# HEATER.net
KiCad netlist of a schematic drawn in Altium Designer
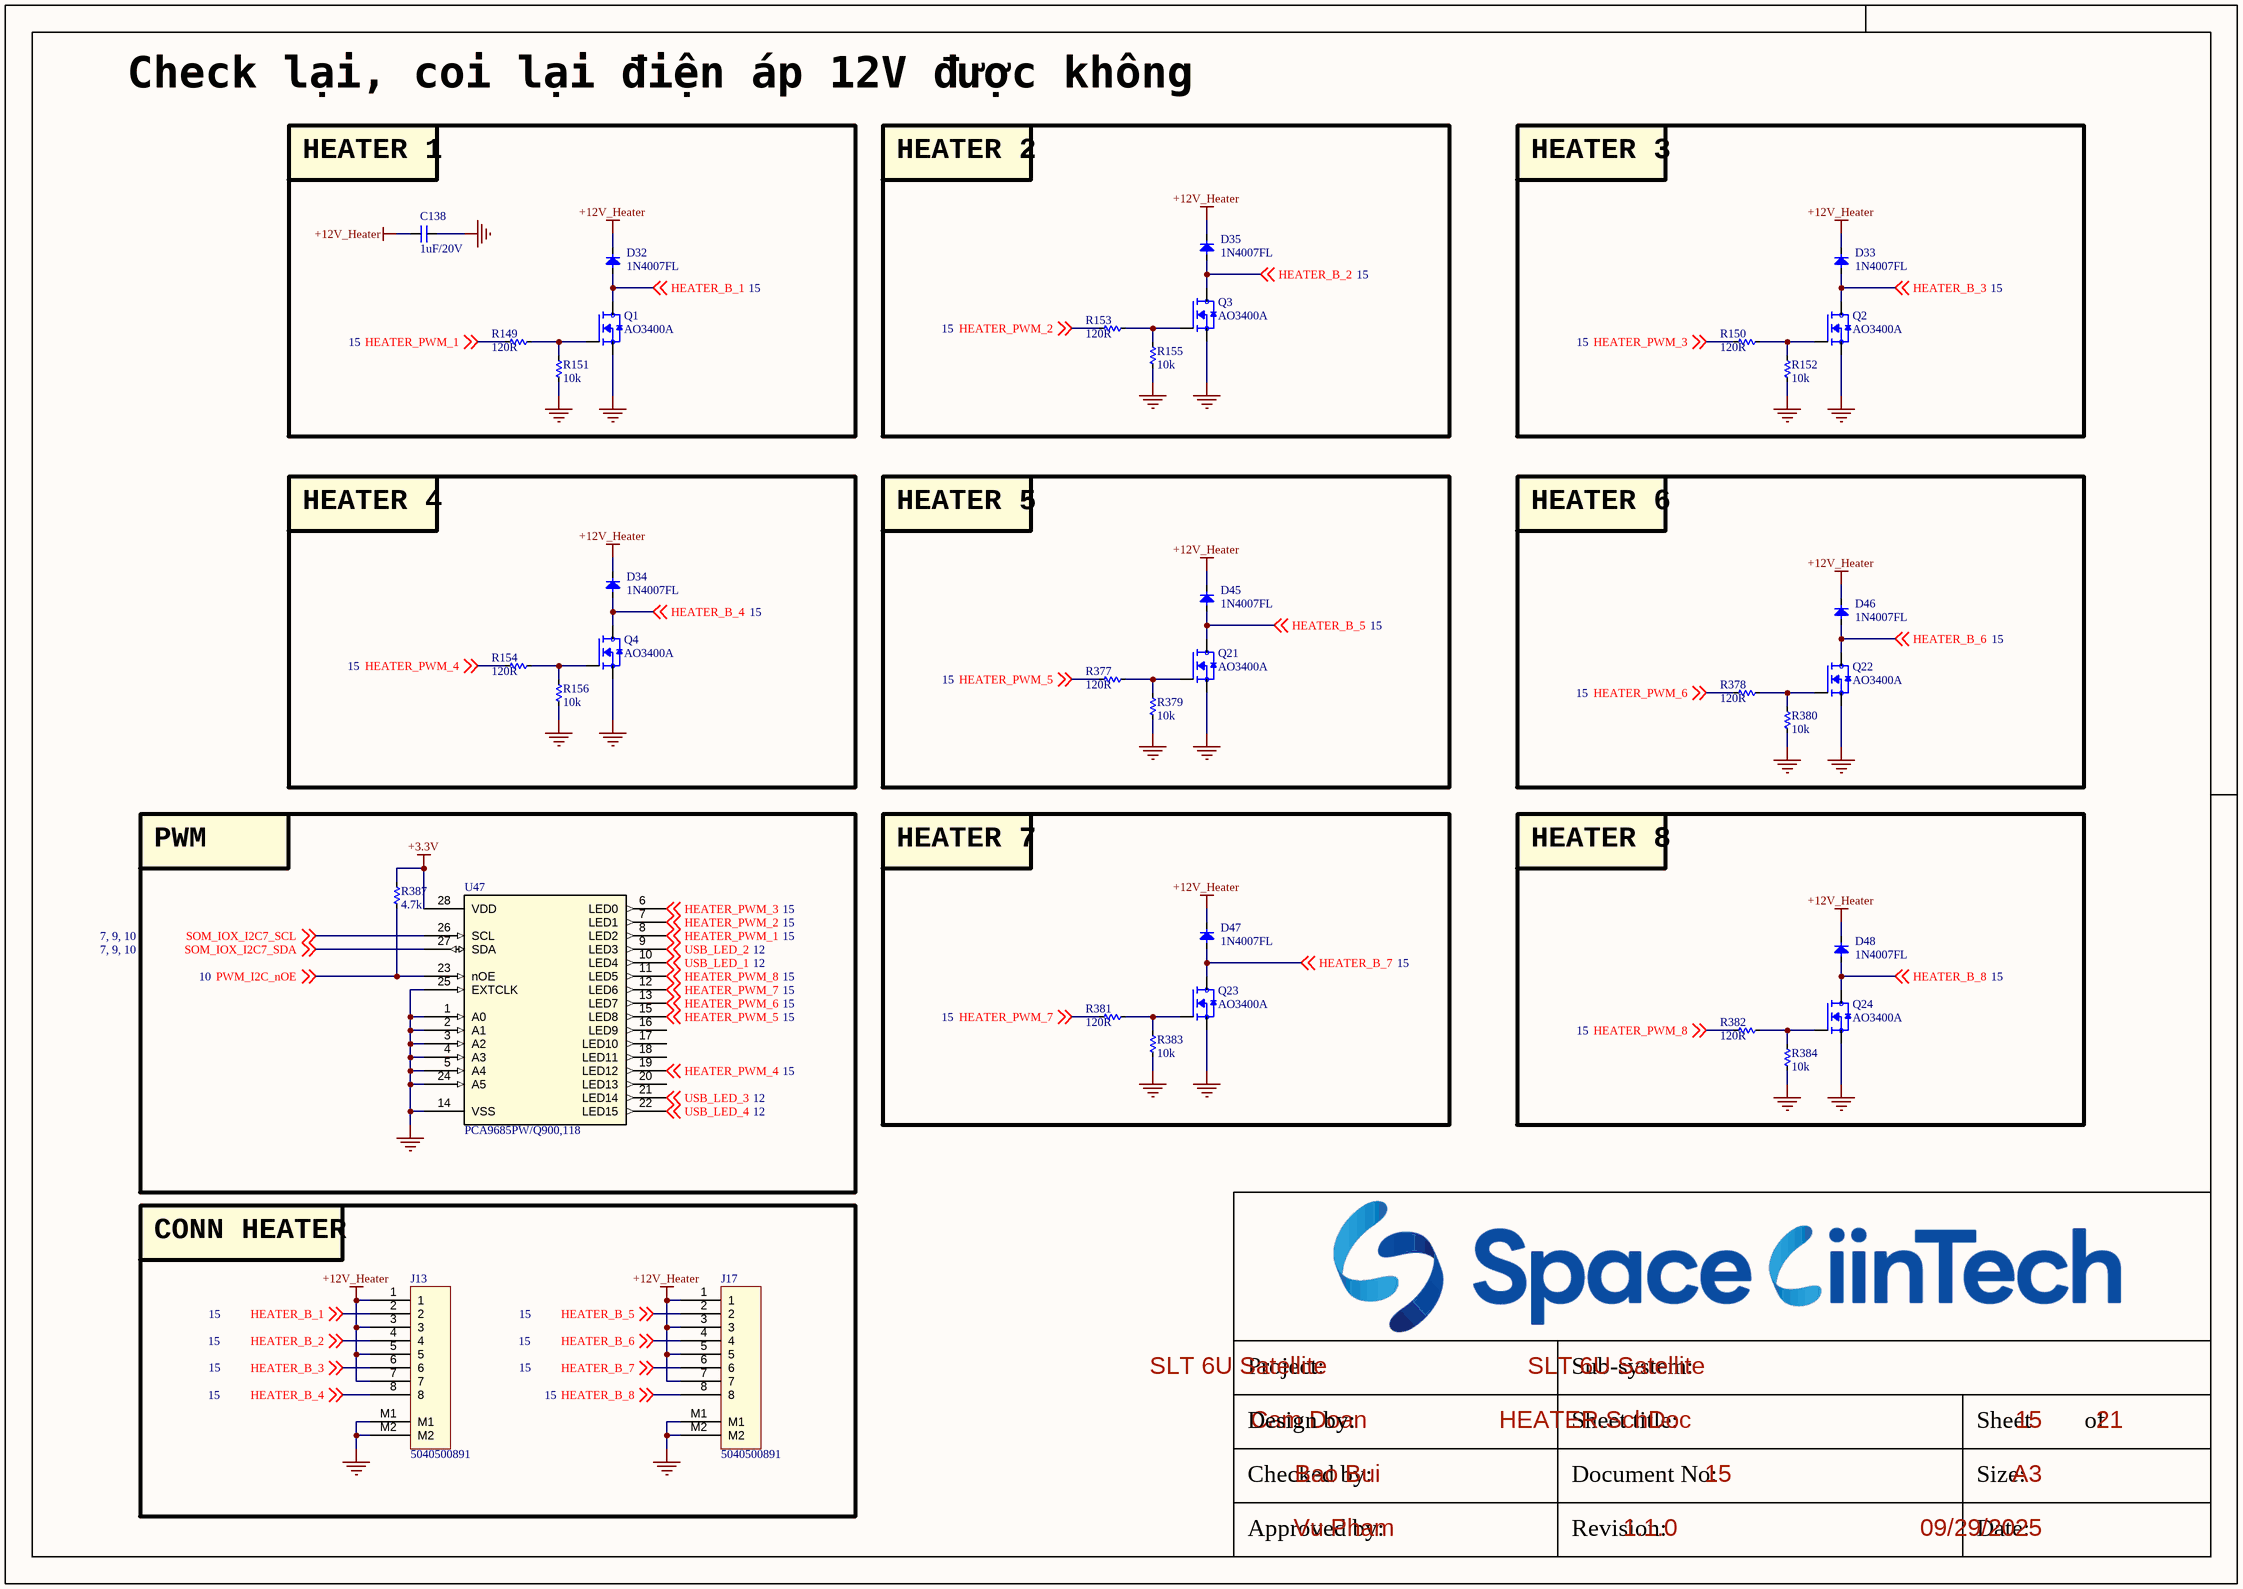
[diagram p0: HEATER.SchDoc]

(export (version "E")
  (design (tool "Eeschema 10.0.6"))
  (components
    (comp (ref "C138")
      (value "1uF/20V")
      (footprint "CAP_C_1005X60")
      (description "CAP CHIP")
      (libsource (lib "LABLIB") (part "_CAP_C_2"))
    )
    (comp (ref "D32")
      (value "1N4007FL")
      (footprint "SOD3717X145N")
      (description "Default Diode")
      (fields (field (name "PUBLISHER") "Altium Limited"))
      (libsource (lib "LABLIB") (part "Diode SMD"))
    )
    (comp (ref "D33")
      (value "1N4007FL")
      (footprint "SOD3717X145N")
      (description "Default Diode")
      (fields (field (name "PUBLISHER") "Altium Limited"))
      (libsource (lib "LABLIB") (part "Diode SMD"))
    )
    (comp (ref "D34")
      (value "1N4007FL")
      (footprint "SOD3717X145N")
      (description "Default Diode")
      (fields (field (name "PUBLISHER") "Altium Limited"))
      (libsource (lib "LABLIB") (part "Diode SMD"))
    )
    (comp (ref "D35")
      (value "1N4007FL")
      (footprint "SOD3717X145N")
      (description "Default Diode")
      (fields (field (name "PUBLISHER") "Altium Limited"))
      (libsource (lib "LABLIB") (part "Diode SMD"))
    )
    (comp (ref "D45")
      (value "1N4007FL")
      (footprint "SOD3717X145N")
      (description "Default Diode")
      (fields (field (name "PUBLISHER") "Altium Limited"))
      (libsource (lib "LABLIB") (part "Diode SMD"))
    )
    (comp (ref "D46")
      (value "1N4007FL")
      (footprint "SOD3717X145N")
      (description "Default Diode")
      (fields (field (name "PUBLISHER") "Altium Limited"))
      (libsource (lib "LABLIB") (part "Diode SMD"))
    )
    (comp (ref "D47")
      (value "1N4007FL")
      (footprint "SOD3717X145N")
      (description "Default Diode")
      (fields (field (name "PUBLISHER") "Altium Limited"))
      (libsource (lib "LABLIB") (part "Diode SMD"))
    )
    (comp (ref "D48")
      (value "1N4007FL")
      (footprint "SOD3717X145N")
      (description "Default Diode")
      (fields (field (name "PUBLISHER") "Altium Limited"))
      (libsource (lib "LABLIB") (part "Diode SMD"))
    )
    (comp (ref "J13")
      (value "5040500891")
      (footprint "MOLEX_5040500891")
      (libsource (lib "LABLIB") (part "Header 8x1_2M"))
    )
    (comp (ref "J17")
      (value "5040500891")
      (footprint "MOLEX_5040500891")
      (libsource (lib "LABLIB") (part "Header 8x1_2M"))
    )
    (comp (ref "Q1")
      (value "AO3400A")
      (footprint "SOT95P240X120-3N")
      (description "N-Channel 30 V 5.7A (Ta) 1.4W (Ta) Surface Mount SOT-23-3")
      (fields (field (name "MF") "Alpha & Omega Semiconductor"))
      (libsource (lib "new_component") (part "MOSFET_N"))
    )
    (comp (ref "Q2")
      (value "AO3400A")
      (footprint "SOT95P240X120-3N")
      (description "N-Channel 30 V 5.7A (Ta) 1.4W (Ta) Surface Mount SOT-23-3")
      (fields (field (name "MF") "Alpha & Omega Semiconductor"))
      (libsource (lib "new_component") (part "MOSFET_N"))
    )
    (comp (ref "Q3")
      (value "AO3400A")
      (footprint "SOT95P240X120-3N")
      (description "N-Channel 30 V 5.7A (Ta) 1.4W (Ta) Surface Mount SOT-23-3")
      (fields (field (name "MF") "Alpha & Omega Semiconductor"))
      (libsource (lib "new_component") (part "MOSFET_N"))
    )
    (comp (ref "Q4")
      (value "AO3400A")
      (footprint "SOT95P240X120-3N")
      (description "N-Channel 30 V 5.7A (Ta) 1.4W (Ta) Surface Mount SOT-23-3")
      (fields (field (name "MF") "Alpha & Omega Semiconductor"))
      (libsource (lib "new_component") (part "MOSFET_N"))
    )
    (comp (ref "Q21")
      (value "AO3400A")
      (footprint "SOT95P240X120-3N")
      (description "N-Channel 30 V 5.7A (Ta) 1.4W (Ta) Surface Mount SOT-23-3")
      (fields (field (name "MF") "Alpha & Omega Semiconductor"))
      (libsource (lib "new_component") (part "MOSFET_N"))
    )
    (comp (ref "Q22")
      (value "AO3400A")
      (footprint "SOT95P240X120-3N")
      (description "N-Channel 30 V 5.7A (Ta) 1.4W (Ta) Surface Mount SOT-23-3")
      (fields (field (name "MF") "Alpha & Omega Semiconductor"))
      (libsource (lib "new_component") (part "MOSFET_N"))
    )
    (comp (ref "Q23")
      (value "AO3400A")
      (footprint "SOT95P240X120-3N")
      (description "N-Channel 30 V 5.7A (Ta) 1.4W (Ta) Surface Mount SOT-23-3")
      (fields (field (name "MF") "Alpha & Omega Semiconductor"))
      (libsource (lib "new_component") (part "MOSFET_N"))
    )
    (comp (ref "Q24")
      (value "AO3400A")
      (footprint "SOT95P240X120-3N")
      (description "N-Channel 30 V 5.7A (Ta) 1.4W (Ta) Surface Mount SOT-23-3")
      (fields (field (name "MF") "Alpha & Omega Semiconductor"))
      (libsource (lib "new_component") (part "MOSFET_N"))
    )
    (comp (ref "R149")
      (value "120R")
      (footprint "RES_C_1005X40")
      (description "RES")
      (libsource (lib "LABLIB") (part "_RES_B_2"))
    )
    (comp (ref "R150")
      (value "120R")
      (footprint "RES_C_1005X40")
      (description "RES")
      (libsource (lib "LABLIB") (part "_RES_B_2"))
    )
    (comp (ref "R151")
      (value "10k")
      (footprint "RES_C_1005X40")
      (description "RES")
      (libsource (lib "LABLIB") (part "_RES_B_2"))
    )
    (comp (ref "R152")
      (value "10k")
      (footprint "RES_C_1005X40")
      (description "RES")
      (libsource (lib "LABLIB") (part "_RES_B_2"))
    )
    (comp (ref "R153")
      (value "120R")
      (footprint "RES_C_1005X40")
      (description "RES")
      (libsource (lib "LABLIB") (part "_RES_B_2"))
    )
    (comp (ref "R154")
      (value "120R")
      (footprint "RES_C_1005X40")
      (description "RES")
      (libsource (lib "LABLIB") (part "_RES_B_2"))
    )
    (comp (ref "R155")
      (value "10k")
      (footprint "RES_C_1005X40")
      (description "RES")
      (libsource (lib "LABLIB") (part "_RES_B_2"))
    )
    (comp (ref "R156")
      (value "10k")
      (footprint "RES_C_1005X40")
      (description "RES")
      (libsource (lib "LABLIB") (part "_RES_B_2"))
    )
    (comp (ref "R377")
      (value "120R")
      (footprint "RES_C_1005X40")
      (description "RES")
      (libsource (lib "LABLIB") (part "_RES_B_2"))
    )
    (comp (ref "R378")
      (value "120R")
      (footprint "RES_C_1005X40")
      (description "RES")
      (libsource (lib "LABLIB") (part "_RES_B_2"))
    )
    (comp (ref "R379")
      (value "10k")
      (footprint "RES_C_1005X40")
      (description "RES")
      (libsource (lib "LABLIB") (part "_RES_B_2"))
    )
    (comp (ref "R380")
      (value "10k")
      (footprint "RES_C_1005X40")
      (description "RES")
      (libsource (lib "LABLIB") (part "_RES_B_2"))
    )
    (comp (ref "R381")
      (value "120R")
      (footprint "RES_C_1005X40")
      (description "RES")
      (libsource (lib "LABLIB") (part "_RES_B_2"))
    )
    (comp (ref "R382")
      (value "120R")
      (footprint "RES_C_1005X40")
      (description "RES")
      (libsource (lib "LABLIB") (part "_RES_B_2"))
    )
    (comp (ref "R383")
      (value "10k")
      (footprint "RES_C_1005X40")
      (description "RES")
      (libsource (lib "LABLIB") (part "_RES_B_2"))
    )
    (comp (ref "R384")
      (value "10k")
      (footprint "RES_C_1005X40")
      (description "RES")
      (libsource (lib "LABLIB") (part "_RES_B_2"))
    )
    (comp (ref "R387")
      (value "4.7k")
      (footprint "RES_C_1005X40")
      (description "RES")
      (libsource (lib "LABLIB") (part "_RES_B_2"))
    )
    (comp (ref "U47")
      (value "PCA9685PW/Q900,118")
      (footprint "TSSOP28_SOT361-1_NXP")
      (description "No Description Available")
      (fields (field (name "COPYRIGHT") "Copyright (C) 2025 Ultra Librarian. All rights reserved."))
      (libsource (lib "LABLIB") (part "IC_PWM_PCA9685PW/Q900,118"))
    )
  )
  (nets
    (net (code "1") (name "+3.3V") (class "Default")
      (node (ref "R387") (pin "2") (pinfunction "2_2") (pintype "passive"))
      (node (ref "U47") (pin "28") (pinfunction "VDD_28") (pintype "power_in"))
    )
    (net (code "2") (name "+12V_Heater") (class "Default")
      (node (ref "C138") (pin "2") (pinfunction "2_2") (pintype "passive"))
      (node (ref "D32") (pin "1") (pinfunction "K_1") (pintype "passive"))
      (node (ref "D33") (pin "1") (pinfunction "K_1") (pintype "passive"))
      (node (ref "D34") (pin "1") (pinfunction "K_1") (pintype "passive"))
      (node (ref "D35") (pin "1") (pinfunction "K_1") (pintype "passive"))
      (node (ref "D45") (pin "1") (pinfunction "K_1") (pintype "passive"))
      (node (ref "D46") (pin "1") (pinfunction "K_1") (pintype "passive"))
      (node (ref "D47") (pin "1") (pinfunction "K_1") (pintype "passive"))
      (node (ref "D48") (pin "1") (pinfunction "K_1") (pintype "passive"))
      (node (ref "J13") (pin "1") (pinfunction "1_1") (pintype "passive"))
      (node (ref "J13") (pin "3") (pinfunction "3_3") (pintype "passive"))
      (node (ref "J13") (pin "5") (pinfunction "5_5") (pintype "passive"))
      (node (ref "J13") (pin "7") (pinfunction "7_7") (pintype "passive"))
      (node (ref "J17") (pin "1") (pinfunction "1_1") (pintype "passive"))
      (node (ref "J17") (pin "3") (pinfunction "3_3") (pintype "passive"))
      (node (ref "J17") (pin "5") (pinfunction "5_5") (pintype "passive"))
      (node (ref "J17") (pin "7") (pinfunction "7_7") (pintype "passive"))
    )
    (net (code "3") (name "GND") (class "Default")
      (node (ref "C138") (pin "1") (pinfunction "1_1") (pintype "passive"))
      (node (ref "J13") (pin "M1") (pinfunction "M1_M1") (pintype "passive"))
      (node (ref "J13") (pin "M2") (pinfunction "M2_M2") (pintype "passive"))
      (node (ref "J17") (pin "M1") (pinfunction "M1_M1") (pintype "passive"))
      (node (ref "J17") (pin "M2") (pinfunction "M2_M2") (pintype "passive"))
      (node (ref "Q1") (pin "2") (pinfunction "S_2") (pintype "passive"))
      (node (ref "Q2") (pin "2") (pinfunction "S_2") (pintype "passive"))
      (node (ref "Q21") (pin "2") (pinfunction "S_2") (pintype "passive"))
      (node (ref "Q22") (pin "2") (pinfunction "S_2") (pintype "passive"))
      (node (ref "Q23") (pin "2") (pinfunction "S_2") (pintype "passive"))
      (node (ref "Q24") (pin "2") (pinfunction "S_2") (pintype "passive"))
      (node (ref "Q3") (pin "2") (pinfunction "S_2") (pintype "passive"))
      (node (ref "Q4") (pin "2") (pinfunction "S_2") (pintype "passive"))
      (node (ref "R151") (pin "1") (pinfunction "1_1") (pintype "passive"))
      (node (ref "R152") (pin "1") (pinfunction "1_1") (pintype "passive"))
      (node (ref "R155") (pin "1") (pinfunction "1_1") (pintype "passive"))
      (node (ref "R156") (pin "1") (pinfunction "1_1") (pintype "passive"))
      (node (ref "R379") (pin "1") (pinfunction "1_1") (pintype "passive"))
      (node (ref "R380") (pin "1") (pinfunction "1_1") (pintype "passive"))
      (node (ref "R383") (pin "1") (pinfunction "1_1") (pintype "passive"))
      (node (ref "R384") (pin "1") (pinfunction "1_1") (pintype "passive"))
      (node (ref "U47") (pin "1") (pinfunction "A0_1") (pintype "input"))
      (node (ref "U47") (pin "14") (pinfunction "VSS_14") (pintype "power_in"))
      (node (ref "U47") (pin "2") (pinfunction "A1_2") (pintype "input"))
      (node (ref "U47") (pin "24") (pinfunction "A5_24") (pintype "input"))
      (node (ref "U47") (pin "25") (pinfunction "EXTCLK_25") (pintype "input"))
      (node (ref "U47") (pin "3") (pinfunction "A2_3") (pintype "input"))
      (node (ref "U47") (pin "4") (pinfunction "A3_4") (pintype "input"))
      (node (ref "U47") (pin "5") (pinfunction "A4_5") (pintype "input"))
    )
    (net (code "4") (name "HEATER_B_1") (class "Default")
      (node (ref "D32") (pin "2") (pinfunction "A_2") (pintype "passive"))
      (node (ref "J13") (pin "2") (pinfunction "2_2") (pintype "passive"))
      (node (ref "Q1") (pin "3") (pinfunction "D_3") (pintype "passive"))
    )
    (net (code "5") (name "HEATER_B_2") (class "Default")
      (node (ref "D35") (pin "2") (pinfunction "A_2") (pintype "passive"))
      (node (ref "J13") (pin "4") (pinfunction "4_4") (pintype "passive"))
      (node (ref "Q3") (pin "3") (pinfunction "D_3") (pintype "passive"))
    )
    (net (code "6") (name "HEATER_B_3") (class "Default")
      (node (ref "D33") (pin "2") (pinfunction "A_2") (pintype "passive"))
      (node (ref "J13") (pin "6") (pinfunction "6_6") (pintype "passive"))
      (node (ref "Q2") (pin "3") (pinfunction "D_3") (pintype "passive"))
    )
    (net (code "7") (name "HEATER_B_4") (class "Default")
      (node (ref "D34") (pin "2") (pinfunction "A_2") (pintype "passive"))
      (node (ref "J13") (pin "8") (pinfunction "8_8") (pintype "passive"))
      (node (ref "Q4") (pin "3") (pinfunction "D_3") (pintype "passive"))
    )
    (net (code "8") (name "HEATER_B_5") (class "Default")
      (node (ref "D45") (pin "2") (pinfunction "A_2") (pintype "passive"))
      (node (ref "J17") (pin "2") (pinfunction "2_2") (pintype "passive"))
      (node (ref "Q21") (pin "3") (pinfunction "D_3") (pintype "passive"))
    )
    (net (code "9") (name "HEATER_B_6") (class "Default")
      (node (ref "D46") (pin "2") (pinfunction "A_2") (pintype "passive"))
      (node (ref "J17") (pin "4") (pinfunction "4_4") (pintype "passive"))
      (node (ref "Q22") (pin "3") (pinfunction "D_3") (pintype "passive"))
    )
    (net (code "10") (name "HEATER_B_7") (class "Default")
      (node (ref "D47") (pin "2") (pinfunction "A_2") (pintype "passive"))
      (node (ref "J17") (pin "6") (pinfunction "6_6") (pintype "passive"))
      (node (ref "Q23") (pin "3") (pinfunction "D_3") (pintype "passive"))
    )
    (net (code "11") (name "HEATER_B_8") (class "Default")
      (node (ref "D48") (pin "2") (pinfunction "A_2") (pintype "passive"))
      (node (ref "J17") (pin "8") (pinfunction "8_8") (pintype "passive"))
      (node (ref "Q24") (pin "3") (pinfunction "D_3") (pintype "passive"))
    )
    (net (code "12") (name "HEATER_PWM_1") (class "Default")
      (node (ref "R149") (pin "1") (pinfunction "1_1") (pintype "passive"))
      (node (ref "U47") (pin "8") (pinfunction "LED2_8") (pintype "output"))
    )
    (net (code "13") (name "HEATER_PWM_2") (class "Default")
      (node (ref "R153") (pin "1") (pinfunction "1_1") (pintype "passive"))
      (node (ref "U47") (pin "7") (pinfunction "LED1_7") (pintype "output"))
    )
    (net (code "14") (name "HEATER_PWM_3") (class "Default")
      (node (ref "R150") (pin "1") (pinfunction "1_1") (pintype "passive"))
      (node (ref "U47") (pin "6") (pinfunction "LED0_6") (pintype "output"))
    )
    (net (code "15") (name "HEATER_PWM_4") (class "Default")
      (node (ref "R154") (pin "1") (pinfunction "1_1") (pintype "passive"))
      (node (ref "U47") (pin "19") (pinfunction "LED12_19") (pintype "output"))
    )
    (net (code "16") (name "HEATER_PWM_5") (class "Default")
      (node (ref "R377") (pin "1") (pinfunction "1_1") (pintype "passive"))
      (node (ref "U47") (pin "15") (pinfunction "LED8_15") (pintype "output"))
    )
    (net (code "17") (name "HEATER_PWM_6") (class "Default")
      (node (ref "R378") (pin "1") (pinfunction "1_1") (pintype "passive"))
      (node (ref "U47") (pin "13") (pinfunction "LED7_13") (pintype "output"))
    )
    (net (code "18") (name "HEATER_PWM_7") (class "Default")
      (node (ref "R381") (pin "1") (pinfunction "1_1") (pintype "passive"))
      (node (ref "U47") (pin "12") (pinfunction "LED6_12") (pintype "output"))
    )
    (net (code "19") (name "HEATER_PWM_8") (class "Default")
      (node (ref "R382") (pin "1") (pinfunction "1_1") (pintype "passive"))
      (node (ref "U47") (pin "11") (pinfunction "LED5_11") (pintype "output"))
    )
    (net (code "20") (name "Net-(Q1-G)") (class "Default")
      (node (ref "Q1") (pin "1") (pinfunction "G_1") (pintype "passive"))
      (node (ref "R149") (pin "2") (pinfunction "2_2") (pintype "passive"))
      (node (ref "R151") (pin "2") (pinfunction "2_2") (pintype "passive"))
    )
    (net (code "21") (name "Net-(Q2-G)") (class "Default")
      (node (ref "Q2") (pin "1") (pinfunction "G_1") (pintype "passive"))
      (node (ref "R150") (pin "2") (pinfunction "2_2") (pintype "passive"))
      (node (ref "R152") (pin "2") (pinfunction "2_2") (pintype "passive"))
    )
    (net (code "22") (name "Net-(Q3-G)") (class "Default")
      (node (ref "Q3") (pin "1") (pinfunction "G_1") (pintype "passive"))
      (node (ref "R153") (pin "2") (pinfunction "2_2") (pintype "passive"))
      (node (ref "R155") (pin "2") (pinfunction "2_2") (pintype "passive"))
    )
    (net (code "23") (name "Net-(Q4-G)") (class "Default")
      (node (ref "Q4") (pin "1") (pinfunction "G_1") (pintype "passive"))
      (node (ref "R154") (pin "2") (pinfunction "2_2") (pintype "passive"))
      (node (ref "R156") (pin "2") (pinfunction "2_2") (pintype "passive"))
    )
    (net (code "24") (name "Net-(Q21-G)") (class "Default")
      (node (ref "Q21") (pin "1") (pinfunction "G_1") (pintype "passive"))
      (node (ref "R377") (pin "2") (pinfunction "2_2") (pintype "passive"))
      (node (ref "R379") (pin "2") (pinfunction "2_2") (pintype "passive"))
    )
    (net (code "25") (name "Net-(Q22-G)") (class "Default")
      (node (ref "Q22") (pin "1") (pinfunction "G_1") (pintype "passive"))
      (node (ref "R378") (pin "2") (pinfunction "2_2") (pintype "passive"))
      (node (ref "R380") (pin "2") (pinfunction "2_2") (pintype "passive"))
    )
    (net (code "26") (name "Net-(Q23-G)") (class "Default")
      (node (ref "Q23") (pin "1") (pinfunction "G_1") (pintype "passive"))
      (node (ref "R381") (pin "2") (pinfunction "2_2") (pintype "passive"))
      (node (ref "R383") (pin "2") (pinfunction "2_2") (pintype "passive"))
    )
    (net (code "27") (name "Net-(Q24-G)") (class "Default")
      (node (ref "Q24") (pin "1") (pinfunction "G_1") (pintype "passive"))
      (node (ref "R382") (pin "2") (pinfunction "2_2") (pintype "passive"))
      (node (ref "R384") (pin "2") (pinfunction "2_2") (pintype "passive"))
    )
    (net (code "28") (name "PWM_I2C_nOE") (class "Default")
      (node (ref "R387") (pin "1") (pinfunction "1_1") (pintype "passive"))
      (node (ref "U47") (pin "23") (pinfunction "nOE_23") (pintype "input"))
    )
    (net (code "29") (name "SOM_IOX_I2C7_SCL") (class "Default")
      (node (ref "U47") (pin "26") (pinfunction "SCL_26") (pintype "input"))
    )
    (net (code "30") (name "SOM_IOX_I2C7_SDA") (class "Default")
      (node (ref "U47") (pin "27") (pinfunction "SDA_27") (pintype "bidirectional"))
    )
    (net (code "31") (name "USB_LED_1") (class "Default")
      (node (ref "U47") (pin "10") (pinfunction "LED4_10") (pintype "output"))
    )
    (net (code "32") (name "USB_LED_2") (class "Default")
      (node (ref "U47") (pin "9") (pinfunction "LED3_9") (pintype "output"))
    )
    (net (code "33") (name "USB_LED_3") (class "Default")
      (node (ref "U47") (pin "21") (pinfunction "LED14_21") (pintype "output"))
    )
    (net (code "34") (name "USB_LED_4") (class "Default")
      (node (ref "U47") (pin "22") (pinfunction "LED15_22") (pintype "output"))
    )
    (net (code "35") (name "unconnected-(U47-LED9-Pad16)") (class "Default")
      (node (ref "U47") (pin "16") (pinfunction "LED9_16") (pintype "output"))
    )
    (net (code "36") (name "unconnected-(U47-LED10-Pad17)") (class "Default")
      (node (ref "U47") (pin "17") (pinfunction "LED10_17") (pintype "output"))
    )
    (net (code "37") (name "unconnected-(U47-LED11-Pad18)") (class "Default")
      (node (ref "U47") (pin "18") (pinfunction "LED11_18") (pintype "output"))
    )
    (net (code "38") (name "unconnected-(U47-LED13-Pad20)") (class "Default")
      (node (ref "U47") (pin "20") (pinfunction "LED13_20") (pintype "output"))
    )
  )
)
